# ESPSmartPlug1.net
KiCad netlist of a schematic drawn in Altium Designer
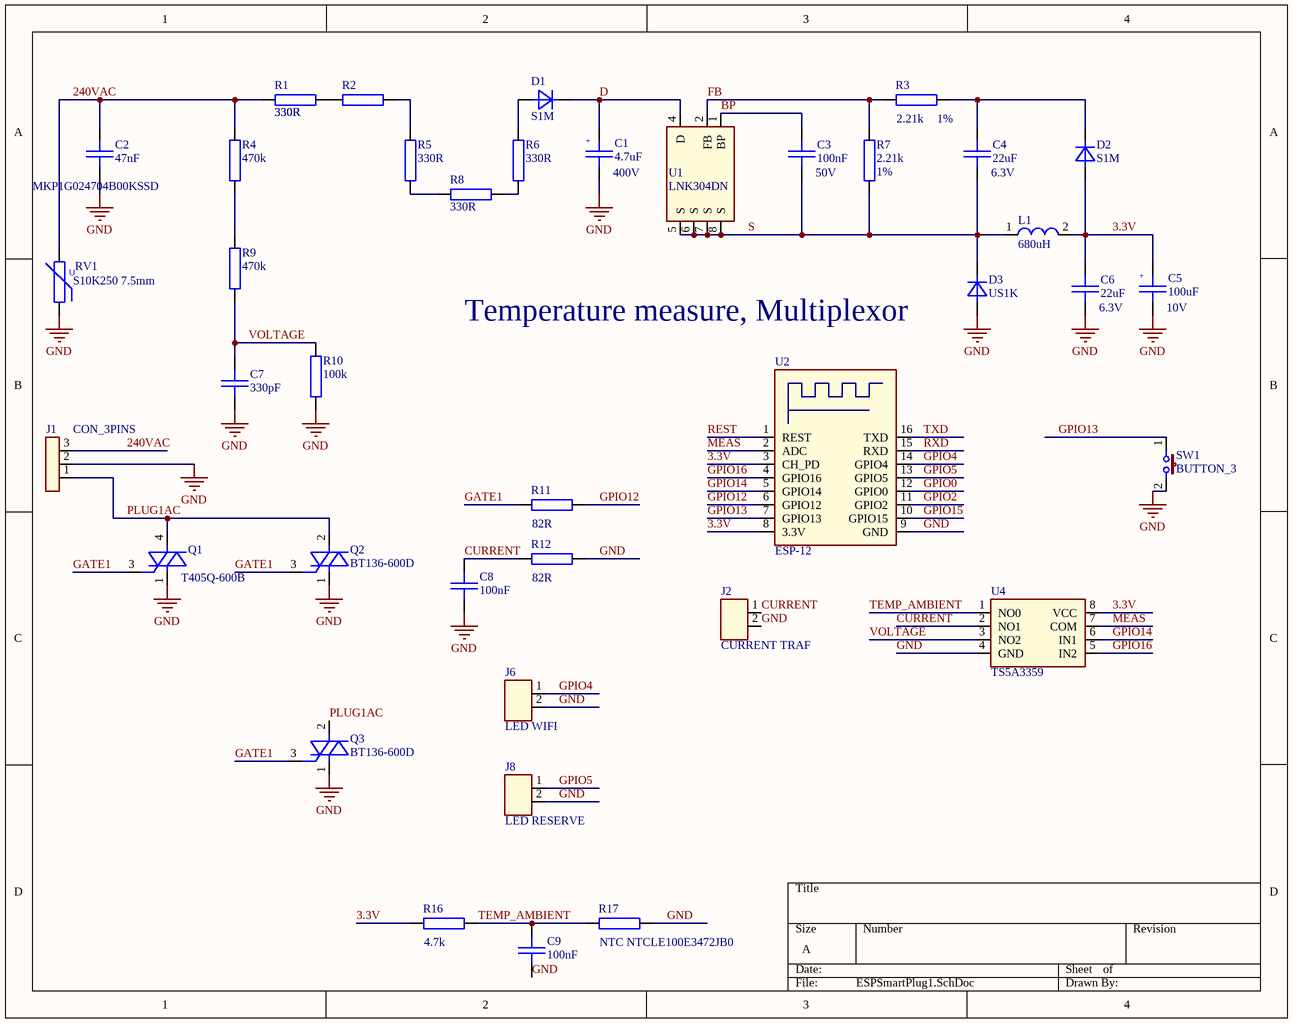
[diagram p0: ESPSmartPlug1.SchDoc]

(export (version "E")
  (design (tool "Eeschema 10.0.6"))
  (components
    (comp (ref "C1")
      (value "4.7uF")
      (footprint "SMD_CAPAE1030X1050N")
      (fields (field (name "VOLTAGE") "400V"))
      (libsource (lib "DLV") (part "C_POL"))
    )
    (comp (ref "C2")
      (value "47nF")
      (footprint "PTH_CAPA1500-630X1850X1550")
      (description "47nF 310V")
      (fields (field (name "MANUFACTURER_NUMBER") "MKP1G024704B00KSSD"))
      (libsource (lib "DLV") (part "C"))
    )
    (comp (ref "C3")
      (value "100nF")
      (footprint "SMD_0603_CAPC1608X95N")
      (fields (field (name "VOLTAGE") "50V"))
      (libsource (lib "DLV") (part "C"))
    )
    (comp (ref "C4")
      (value "22uF")
      (footprint "SMD_0805_CAPC2012X95N")
      (fields (field (name "VOLTAGE") "6.3V"))
      (libsource (lib "DLV") (part "C"))
    )
    (comp (ref "C5")
      (value "100uF")
      (footprint "SMD_CAPAE660X550N")
      (fields (field (name "VOLTAGE") "10V"))
      (libsource (lib "DLV") (part "C_POL"))
    )
    (comp (ref "C6")
      (value "22uF")
      (footprint "SMD_0805_CAPC2012X95N")
      (fields (field (name "VOLTAGE") "6.3V"))
      (libsource (lib "DLV") (part "C"))
    )
    (comp (ref "C7") (value "330pF") (footprint "SMD_0603_CAPC1608X95N") (libsource (lib "DLV") (part "C")))
    (comp (ref "C8") (value "100nF") (footprint "SMD_0805_CAPC2012X95N") (libsource (lib "DLV") (part "C")))
    (comp (ref "C9") (value "100nF") (footprint "SMD_0603_CAPC1608X95N") (libsource (lib "DLV") (part "C")))
    (comp (ref "D1") (value "S1M") (footprint "SMD_DO214AC_SMA") (libsource (lib "DLV") (part "D")))
    (comp (ref "D2") (value "S1M") (footprint "SMD_DO214AC_SMA") (libsource (lib "DLV") (part "D")))
    (comp (ref "D3") (value "US1K") (footprint "SMD_DO214AC_SMA") (libsource (lib "DLV") (part "D")))
    (comp (ref "J1")
      (value "CON_3PINS")
      (footprint "PTH_HDRV03W11060P500_1X03")
      (libsource (lib "DLV") (part "CON_3PINS"))
    )
    (comp (ref "J2")
      (value "CURRENT TRAF")
      (footprint "PTH_HDRV02W64P254_1X02")
      (libsource (lib "DLV") (part "CON_2PINS"))
    )
    (comp (ref "J6")
      (value "LED WIFI")
      (footprint "SMD_LED_LAA67F")
      (libsource (lib "DLV") (part "CON_2PINS"))
    )
    (comp (ref "J8")
      (value "LED RESERVE")
      (footprint "SMD_LED_LAA67F")
      (libsource (lib "DLV") (part "CON_2PINS"))
    )
    (comp (ref "L1") (value "680uH") (footprint "SMD_INDC101101X480N") (libsource (lib "*") (part "L")))
    (comp (ref "Q1")
      (value "T405Q-600B")
      (footprint "SMD_TO229P991X239-4N_DPAK")
      (libsource (lib "DLV") (part "THYR_T11G3T24"))
    )
    (comp (ref "Q2")
      (value "BT136-600D")
      (footprint "PTH_TO220AB")
      (libsource (lib "DLV") (part "THYR_T11T22G3"))
    )
    (comp (ref "Q3")
      (value "BT136-600D")
      (footprint "PTH_TO220AB")
      (libsource (lib "DLV") (part "THYR_T11T22G3"))
    )
    (comp (ref "R1") (value "330R") (footprint "SMD_1206_RESC3216X102N") (libsource (lib "DLV") (part "R")))
    (comp (ref "R2") (value "330R") (footprint "SMD_1206_RESC3216X102N") (libsource (lib "DLV") (part "R")))
    (comp (ref "R3")
      (value "2.21k")
      (footprint "SMD_0603_RESC1608X55N")
      (fields (field (name "TOLERANCE") "1%"))
      (libsource (lib "DLV") (part "R"))
    )
    (comp (ref "R4") (value "470k") (footprint "SMD_1206_RESC3216X102N") (libsource (lib "DLV") (part "R")))
    (comp (ref "R5") (value "330R") (footprint "SMD_1206_RESC3216X102N") (libsource (lib "DLV") (part "R")))
    (comp (ref "R6") (value "330R") (footprint "SMD_1206_RESC3216X102N") (libsource (lib "DLV") (part "R")))
    (comp (ref "R7")
      (value "2.21k")
      (footprint "SMD_0603_RESC1608X55N")
      (fields (field (name "TOLERANCE") "1%"))
      (libsource (lib "DLV") (part "R"))
    )
    (comp (ref "R8") (value "330R") (footprint "SMD_1206_RESC3216X102N") (libsource (lib "DLV") (part "R")))
    (comp (ref "R9") (value "470k") (footprint "SMD_1206_RESC3216X102N") (libsource (lib "DLV") (part "R")))
    (comp (ref "R10") (value "100k") (footprint "SMD_0603_RESC1608X55N") (libsource (lib "DLV") (part "R")))
    (comp (ref "R11")
      (value "82R")
      (footprint "SMD_0603_RESC1608X55N")
      (fields (field (name "TOLERANCE") "5%"))
      (libsource (lib "DLV") (part "R"))
    )
    (comp (ref "R12")
      (value "82R")
      (footprint "SMD_0603_RESC1608X55N")
      (fields (field (name "TOLERANCE") "5%"))
      (libsource (lib "DLV") (part "R"))
    )
    (comp (ref "R16")
      (value "4.7k")
      (footprint "SMD_0603_RESC1608X55N")
      (fields (field (name "TOLERANCE") "5%"))
      (libsource (lib "DLV") (part "R"))
    )
    (comp (ref "R17")
      (value "NTC NTCLE100E3472JB0")
      (footprint "PTH_CAPRR500W60L500T400H800A")
      (fields (field (name "TOLERANCE") "5%"))
      (libsource (lib "DLV") (part "R"))
    )
    (comp (ref "RV1")
      (value "S10K250 7.5mm")
      (footprint "PTH_VAR_S10K275")
      (libsource (lib "DLV") (part "VARISTOR"))
    )
    (comp (ref "SW1")
      (value "BUTTON_3")
      (footprint "PTH_SWI_TACT-TS6601V")
      (libsource (lib "DLV") (part "BUTTON_3"))
    )
    (comp (ref "U1")
      (value "LNK304DN")
      (footprint "SMD_SOIC127P600X175-7N")
      (libsource (lib "DLV") (part "IC_LNK302-306D_SO-8C"))
    )
    (comp (ref "U2")
      (value "ESP-12")
      (footprint "SMD_MOD_ESP_12")
      (libsource (lib "DLV") (part "MOD_ESP-12"))
    )
    (comp (ref "U4")
      (value "TS5A3359")
      (footprint "SMD_SOT765-1_SOP50P310X100-8N")
      (description "Analog Multiplexor 3-Channel")
      (libsource (lib "DLV") (part "IC_TS5A3359"))
    )
  )
  (nets
    (net (code "1") (name "/3.3V") (class "Default")
      (node (ref "C5") (pin "1") (pinfunction "1_1") (pintype "passive"))
      (node (ref "C6") (pin "1") (pinfunction "1_1") (pintype "passive"))
      (node (ref "D2") (pin "2") (pinfunction "A_2") (pintype "passive"))
      (node (ref "L1") (pin "2") (pinfunction "2_2") (pintype "passive"))
      (node (ref "R16") (pin "1") (pinfunction "1_1") (pintype "passive"))
      (node (ref "U2") (pin "3") (pinfunction "CH_PD_3") (pintype "passive"))
      (node (ref "U2") (pin "8") (pinfunction "3.3V_8") (pintype "passive"))
      (node (ref "U4") (pin "8") (pinfunction "VCC_8") (pintype "passive"))
    )
    (net (code "2") (name "/240VAC") (class "Default")
      (node (ref "C2") (pin "1") (pinfunction "1_1") (pintype "passive"))
      (node (ref "J1") (pin "3") (pinfunction "3_3") (pintype "passive"))
      (node (ref "R1") (pin "2") (pinfunction "2_2") (pintype "passive"))
      (node (ref "R4") (pin "2") (pinfunction "2_2") (pintype "passive"))
      (node (ref "RV1") (pin "1") (pinfunction "1_1") (pintype "passive"))
    )
    (net (code "3") (name "/BP") (class "Default")
      (node (ref "C3") (pin "1") (pinfunction "1_1") (pintype "passive"))
      (node (ref "U1") (pin "1") (pinfunction "BP_1") (pintype "passive"))
    )
    (net (code "4") (name "/CURRENT") (class "Default")
      (node (ref "C8") (pin "1") (pinfunction "1_1") (pintype "passive"))
      (node (ref "J2") (pin "1") (pinfunction "1_1") (pintype "passive"))
      (node (ref "R12") (pin "1") (pinfunction "1_1") (pintype "passive"))
      (node (ref "U4") (pin "2") (pinfunction "NO1_2") (pintype "passive"))
    )
    (net (code "5") (name "/D") (class "Default")
      (node (ref "C1") (pin "1") (pinfunction "1_1") (pintype "passive"))
      (node (ref "D1") (pin "1") (pinfunction "C_1") (pintype "passive"))
      (node (ref "U1") (pin "4") (pinfunction "D_4") (pintype "passive"))
    )
    (net (code "6") (name "/FB") (class "Default")
      (node (ref "R3") (pin "1") (pinfunction "1_1") (pintype "passive"))
      (node (ref "R7") (pin "1") (pinfunction "1_1") (pintype "passive"))
      (node (ref "U1") (pin "2") (pinfunction "FB_2") (pintype "passive"))
    )
    (net (code "7") (name "/GATE1") (class "Default")
      (node (ref "Q1") (pin "3") (pinfunction "G_3") (pintype "passive"))
      (node (ref "Q2") (pin "3") (pinfunction "G_3") (pintype "passive"))
      (node (ref "Q3") (pin "3") (pinfunction "G_3") (pintype "passive"))
      (node (ref "R11") (pin "1") (pinfunction "1_1") (pintype "passive"))
    )
    (net (code "8") (name "/GPIO0") (class "Default")
      (node (ref "U2") (pin "12") (pinfunction "GPIO0_12") (pintype "passive"))
    )
    (net (code "9") (name "/GPIO2") (class "Default")
      (node (ref "U2") (pin "11") (pinfunction "GPIO2_11") (pintype "passive"))
    )
    (net (code "10") (name "/GPIO4") (class "Default")
      (node (ref "J6") (pin "1") (pinfunction "1_1") (pintype "passive"))
      (node (ref "U2") (pin "14") (pinfunction "GPIO4_14") (pintype "passive"))
    )
    (net (code "11") (name "/GPIO5") (class "Default")
      (node (ref "J8") (pin "1") (pinfunction "1_1") (pintype "passive"))
      (node (ref "U2") (pin "13") (pinfunction "GPIO5_13") (pintype "passive"))
    )
    (net (code "12") (name "/GPIO12") (class "Default")
      (node (ref "R11") (pin "2") (pinfunction "2_2") (pintype "passive"))
      (node (ref "U2") (pin "6") (pinfunction "GPIO12_6") (pintype "passive"))
    )
    (net (code "13") (name "/GPIO13") (class "Default")
      (node (ref "SW1") (pin "1") (pinfunction "1_1") (pintype "passive"))
      (node (ref "U2") (pin "7") (pinfunction "GPIO13_7") (pintype "passive"))
    )
    (net (code "14") (name "/GPIO14") (class "Default")
      (node (ref "U2") (pin "5") (pinfunction "GPIO14_5") (pintype "passive"))
      (node (ref "U4") (pin "6") (pinfunction "IN1_6") (pintype "passive"))
    )
    (net (code "15") (name "/GPIO15") (class "Default")
      (node (ref "U2") (pin "10") (pinfunction "GPIO15_10") (pintype "passive"))
    )
    (net (code "16") (name "/GPIO16") (class "Default")
      (node (ref "U2") (pin "4") (pinfunction "GPIO16_4") (pintype "passive"))
      (node (ref "U4") (pin "5") (pinfunction "IN2_5") (pintype "passive"))
    )
    (net (code "17") (name "/MEAS") (class "Default")
      (node (ref "U2") (pin "2") (pinfunction "ADC_2") (pintype "passive"))
      (node (ref "U4") (pin "7") (pinfunction "COM_7") (pintype "passive"))
    )
    (net (code "18") (name "/PLUG1AC") (class "Default")
      (node (ref "J1") (pin "1") (pinfunction "1_1") (pintype "passive"))
      (node (ref "Q1") (pin "4") (pinfunction "T2_4") (pintype "passive"))
      (node (ref "Q2") (pin "2") (pinfunction "T2_2") (pintype "passive"))
      (node (ref "Q3") (pin "2") (pinfunction "T2_2") (pintype "passive"))
    )
    (net (code "19") (name "/REST") (class "Default")
      (node (ref "U2") (pin "1") (pinfunction "REST_1") (pintype "passive"))
    )
    (net (code "20") (name "/RXD") (class "Default")
      (node (ref "U2") (pin "15") (pinfunction "RXD_15") (pintype "passive"))
    )
    (net (code "21") (name "/S") (class "Default")
      (node (ref "C3") (pin "2") (pinfunction "2_2") (pintype "passive"))
      (node (ref "C4") (pin "2") (pinfunction "2_2") (pintype "passive"))
      (node (ref "D3") (pin "1") (pinfunction "C_1") (pintype "passive"))
      (node (ref "L1") (pin "1") (pinfunction "1_1") (pintype "passive"))
      (node (ref "R7") (pin "2") (pinfunction "2_2") (pintype "passive"))
      (node (ref "U1") (pin "5") (pinfunction "S_5") (pintype "passive"))
      (node (ref "U1") (pin "6") (pinfunction "S_6") (pintype "passive"))
      (node (ref "U1") (pin "7") (pinfunction "S_7") (pintype "passive"))
      (node (ref "U1") (pin "8") (pinfunction "S_8") (pintype "passive"))
    )
    (net (code "22") (name "/TEMP_AMBIENT") (class "Default")
      (node (ref "C9") (pin "1") (pinfunction "1_1") (pintype "passive"))
      (node (ref "R16") (pin "2") (pinfunction "2_2") (pintype "passive"))
      (node (ref "R17") (pin "1") (pinfunction "1_1") (pintype "passive"))
      (node (ref "U4") (pin "1") (pinfunction "NO0_1") (pintype "passive"))
    )
    (net (code "23") (name "/TXD") (class "Default")
      (node (ref "U2") (pin "16") (pinfunction "TXD_16") (pintype "passive"))
    )
    (net (code "24") (name "/VOLTAGE") (class "Default")
      (node (ref "C7") (pin "1") (pinfunction "1_1") (pintype "passive"))
      (node (ref "R10") (pin "2") (pinfunction "2_2") (pintype "passive"))
      (node (ref "R9") (pin "1") (pinfunction "1_1") (pintype "passive"))
      (node (ref "U4") (pin "3") (pinfunction "NO2_3") (pintype "passive"))
    )
    (net (code "25") (name "GND") (class "Default")
      (node (ref "C1") (pin "2") (pinfunction "2_2") (pintype "passive"))
      (node (ref "C2") (pin "2") (pinfunction "2_2") (pintype "passive"))
      (node (ref "C5") (pin "2") (pinfunction "2_2") (pintype "passive"))
      (node (ref "C6") (pin "2") (pinfunction "2_2") (pintype "passive"))
      (node (ref "C7") (pin "2") (pinfunction "2_2") (pintype "passive"))
      (node (ref "C8") (pin "2") (pinfunction "2_2") (pintype "passive"))
      (node (ref "C9") (pin "2") (pinfunction "2_2") (pintype "passive"))
      (node (ref "D3") (pin "2") (pinfunction "A_2") (pintype "passive"))
      (node (ref "J1") (pin "2") (pinfunction "2_2") (pintype "passive"))
      (node (ref "J2") (pin "2") (pinfunction "2_2") (pintype "passive"))
      (node (ref "J6") (pin "2") (pinfunction "2_2") (pintype "passive"))
      (node (ref "J8") (pin "2") (pinfunction "2_2") (pintype "passive"))
      (node (ref "Q1") (pin "1") (pinfunction "T1_1") (pintype "passive"))
      (node (ref "Q2") (pin "1") (pinfunction "T1_1") (pintype "passive"))
      (node (ref "Q3") (pin "1") (pinfunction "T1_1") (pintype "passive"))
      (node (ref "R10") (pin "1") (pinfunction "1_1") (pintype "passive"))
      (node (ref "R12") (pin "2") (pinfunction "2_2") (pintype "passive"))
      (node (ref "R17") (pin "2") (pinfunction "2_2") (pintype "passive"))
      (node (ref "RV1") (pin "2") (pinfunction "2_2") (pintype "passive"))
      (node (ref "SW1") (pin "2") (pinfunction "2_2") (pintype "passive"))
      (node (ref "U2") (pin "9") (pinfunction "GND_9") (pintype "passive"))
      (node (ref "U4") (pin "4") (pinfunction "GND_4") (pintype "passive"))
    )
    (net (code "26") (name "Net-(D1-A)") (class "Default")
      (node (ref "D1") (pin "2") (pinfunction "A_2") (pintype "passive"))
      (node (ref "R6") (pin "1") (pinfunction "1_1") (pintype "passive"))
    )
    (net (code "27") (name "Net-(D2-C)") (class "Default")
      (node (ref "C4") (pin "1") (pinfunction "1_1") (pintype "passive"))
      (node (ref "D2") (pin "1") (pinfunction "C_1") (pintype "passive"))
      (node (ref "R3") (pin "2") (pinfunction "2_2") (pintype "passive"))
    )
    (net (code "28") (name "Net-(R1-Pad1)") (class "Default")
      (node (ref "R1") (pin "1") (pinfunction "1_1") (pintype "passive"))
      (node (ref "R2") (pin "2") (pinfunction "2_2") (pintype "passive"))
    )
    (net (code "29") (name "Net-(R2-Pad1)") (class "Default")
      (node (ref "R2") (pin "1") (pinfunction "1_1") (pintype "passive"))
      (node (ref "R5") (pin "2") (pinfunction "2_2") (pintype "passive"))
    )
    (net (code "30") (name "Net-(R4-Pad1)") (class "Default")
      (node (ref "R4") (pin "1") (pinfunction "1_1") (pintype "passive"))
      (node (ref "R9") (pin "2") (pinfunction "2_2") (pintype "passive"))
    )
    (net (code "31") (name "Net-(R5-Pad1)") (class "Default")
      (node (ref "R5") (pin "1") (pinfunction "1_1") (pintype "passive"))
      (node (ref "R8") (pin "1") (pinfunction "1_1") (pintype "passive"))
    )
    (net (code "32") (name "Net-(R6-Pad2)") (class "Default")
      (node (ref "R6") (pin "2") (pinfunction "2_2") (pintype "passive"))
      (node (ref "R8") (pin "2") (pinfunction "2_2") (pintype "passive"))
    )
  )
)
